# AFM_QFM_input.net
KiCad netlist of a schematic drawn in EAGLE
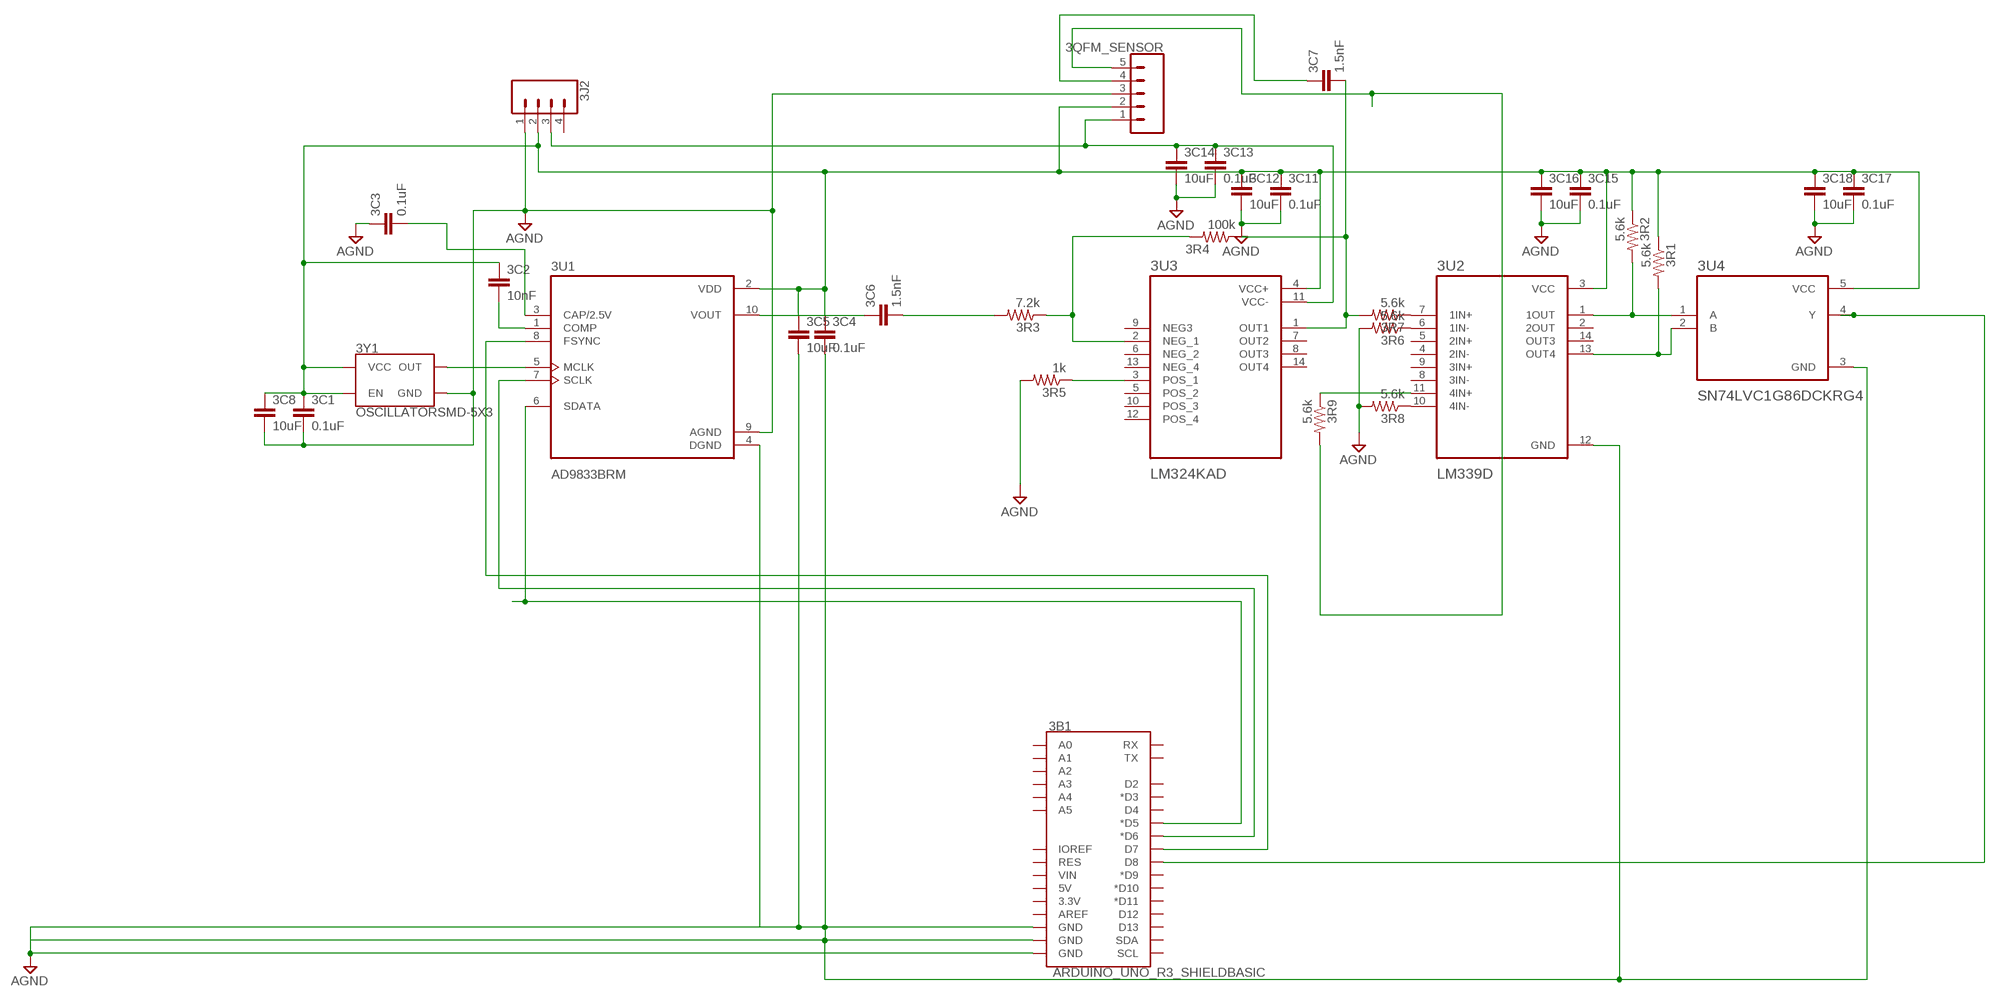
[diagram p0: schematic, sheet 1]

(export (version "E")
  (design (tool "Eeschema 10.0.6"))
  (components
    (comp (ref "3B1")
      (value "ARDUINO_UNO_R3_SHIELDBASIC")
      (footprint "eagle-import:UNO_R3_SHIELD")
      (libsource (lib "eagle-import") (part "ARDUINO_UNO_R3_SHIELDBASIC"))
    )
    (comp (ref "3C1")
      (value "0.1uF")
      (footprint "eagle-import:0603")
      (libsource (lib "eagle-import") (part "0.1UF-0603-100V-10%"))
    )
    (comp (ref "3C2")
      (value "10nF")
      (footprint "eagle-import:0603")
      (libsource (lib "eagle-import") (part "10NF-0603-50V-10%"))
    )
    (comp (ref "3C3")
      (value "0.1uF")
      (footprint "eagle-import:0603")
      (libsource (lib "eagle-import") (part "0.1UF-0603-100V-10%"))
    )
    (comp (ref "3C4")
      (value "0.1uF")
      (footprint "eagle-import:0603")
      (libsource (lib "eagle-import") (part "0.1UF-0603-100V-10%"))
    )
    (comp (ref "3C5")
      (value "10uF")
      (footprint "eagle-import:0805")
      (libsource (lib "eagle-import") (part "10UF-0805-10V-10%"))
    )
    (comp (ref "3C6")
      (value "1.5nF")
      (footprint "eagle-import:C0603")
      (libsource (lib "eagle-import") (part "C-EUC0603"))
    )
    (comp (ref "3C7")
      (value "1.5nF")
      (footprint "eagle-import:C0603")
      (libsource (lib "eagle-import") (part "C-EUC0603"))
    )
    (comp (ref "3C8")
      (value "10uF")
      (footprint "eagle-import:0805")
      (libsource (lib "eagle-import") (part "10UF-0805-10V-10%"))
    )
    (comp (ref "3C11")
      (value "0.1uF")
      (footprint "eagle-import:0603")
      (libsource (lib "eagle-import") (part "0.1UF-0603-100V-10%"))
    )
    (comp (ref "3C12")
      (value "10uF")
      (footprint "eagle-import:0805")
      (libsource (lib "eagle-import") (part "10UF-0805-10V-10%"))
    )
    (comp (ref "3C13")
      (value "0.1uF")
      (footprint "eagle-import:0603")
      (libsource (lib "eagle-import") (part "0.1UF-0603-100V-10%"))
    )
    (comp (ref "3C14")
      (value "10uF")
      (footprint "eagle-import:0805")
      (libsource (lib "eagle-import") (part "10UF-0805-10V-10%"))
    )
    (comp (ref "3C15")
      (value "0.1uF")
      (footprint "eagle-import:0603")
      (libsource (lib "eagle-import") (part "0.1UF-0603-100V-10%"))
    )
    (comp (ref "3C16")
      (value "10uF")
      (footprint "eagle-import:0805")
      (libsource (lib "eagle-import") (part "10UF-0805-10V-10%"))
    )
    (comp (ref "3C17")
      (value "0.1uF")
      (footprint "eagle-import:0603")
      (libsource (lib "eagle-import") (part "0.1UF-0603-100V-10%"))
    )
    (comp (ref "3C18")
      (value "10uF")
      (footprint "eagle-import:0805")
      (libsource (lib "eagle-import") (part "10UF-0805-10V-10%"))
    )
    (comp (ref "3J2")
      (value "CONN_04LONGPADS")
      (footprint "eagle-import:1X04_LONGPADS")
      (libsource (lib "eagle-import") (part "CONN_04LONGPADS"))
    )
    (comp (ref "3QFM_SENSOR")
      (value "CONN_05PTH_LONGPADS")
      (footprint "eagle-import:1X05_LONGPADS")
      (libsource (lib "eagle-import") (part "CONN_05PTH_LONGPADS"))
    )
    (comp (ref "3R1")
      (value "5.6k")
      (footprint "eagle-import:R0603")
      (libsource (lib "eagle-import") (part "R-US_R0603"))
    )
    (comp (ref "3R2")
      (value "5.6k")
      (footprint "eagle-import:R0603")
      (libsource (lib "eagle-import") (part "R-US_R0603"))
    )
    (comp (ref "3R3")
      (value "7.2k")
      (footprint "eagle-import:R0603")
      (libsource (lib "eagle-import") (part "R-US_R0603"))
    )
    (comp (ref "3R4")
      (value "100k")
      (footprint "eagle-import:R0603")
      (libsource (lib "eagle-import") (part "R-US_R0603"))
    )
    (comp (ref "3R5")
      (value "1k")
      (footprint "eagle-import:R0603")
      (libsource (lib "eagle-import") (part "R-US_R0603"))
    )
    (comp (ref "3R6")
      (value "5.6k")
      (footprint "eagle-import:R0603")
      (libsource (lib "eagle-import") (part "R-US_R0603"))
    )
    (comp (ref "3R7")
      (value "5.6k")
      (footprint "eagle-import:R0603")
      (libsource (lib "eagle-import") (part "R-US_R0603"))
    )
    (comp (ref "3R8")
      (value "5.6k")
      (footprint "eagle-import:R0603")
      (libsource (lib "eagle-import") (part "R-US_R0603"))
    )
    (comp (ref "3R9")
      (value "5.6k")
      (footprint "eagle-import:R0603")
      (libsource (lib "eagle-import") (part "R-US_R0603"))
    )
    (comp (ref "3U1")
      (value "AD9833BRM")
      (footprint "eagle-import:SOP50P490X110-10N")
      (fields (field (name "MF") "Analog Devices"))
      (libsource (lib "eagle-import") (part "AD9833BRM"))
    )
    (comp (ref "3U2")
      (value "LM339D")
      (footprint "eagle-import:SOIC127P600X175-14N")
      (fields (field (name "MF") "Texas Instruments"))
      (libsource (lib "eagle-import") (part "LM339D"))
    )
    (comp (ref "3U3")
      (value "LM324KAD")
      (footprint "eagle-import:SOIC127P600X175-14N")
      (fields (field (name "MF") "Texas Instruments"))
      (libsource (lib "eagle-import") (part "LM324KAD"))
    )
    (comp (ref "3U4")
      (value "SN74LVC1G86DCKRG4")
      (footprint "eagle-import:SOT65P210X110-5N")
      (fields (field (name "MF") "Texas Instruments"))
      (libsource (lib "eagle-import") (part "SN74LVC1G86DCKRG4"))
    )
    (comp (ref "3Y1")
      (value "OSCILLATORSMD-5X3")
      (footprint "eagle-import:OSCILLATOR-SMD-5X3.2")
      (libsource (lib "eagle-import") (part "OSCILLATORSMD-5X3"))
    )
  )
  (nets
    (net (code "1") (name "AGND") (class "Default")
      (node (ref "3B1") (pin "GND@0") (pinfunction "GND_GND@0") (pintype "bidirectional"))
      (node (ref "3B1") (pin "GND@1") (pinfunction "GND_GND@1") (pintype "bidirectional"))
      (node (ref "3B1") (pin "GND@2") (pinfunction "GND_GND@2") (pintype "bidirectional"))
      (node (ref "3C1") (pin "2") (pinfunction "2_2") (pintype "passive"))
      (node (ref "3C11") (pin "2") (pinfunction "2_2") (pintype "passive"))
      (node (ref "3C12") (pin "2") (pinfunction "2_2") (pintype "passive"))
      (node (ref "3C13") (pin "2") (pinfunction "2_2") (pintype "passive"))
      (node (ref "3C14") (pin "2") (pinfunction "2_2") (pintype "passive"))
      (node (ref "3C15") (pin "2") (pinfunction "2_2") (pintype "passive"))
      (node (ref "3C16") (pin "2") (pinfunction "2_2") (pintype "passive"))
      (node (ref "3C17") (pin "2") (pinfunction "2_2") (pintype "passive"))
      (node (ref "3C18") (pin "2") (pinfunction "2_2") (pintype "passive"))
      (node (ref "3C3") (pin "1") (pinfunction "1_1") (pintype "passive"))
      (node (ref "3C4") (pin "2") (pinfunction "2_2") (pintype "passive"))
      (node (ref "3C5") (pin "2") (pinfunction "2_2") (pintype "passive"))
      (node (ref "3C8") (pin "2") (pinfunction "2_2") (pintype "passive"))
      (node (ref "3J2") (pin "1") (pinfunction "1_1") (pintype "passive"))
      (node (ref "3QFM_SENSOR") (pin "3") (pinfunction "3_3") (pintype "passive"))
      (node (ref "3R5") (pin "2") (pinfunction "2_2") (pintype "passive"))
      (node (ref "3R6") (pin "2") (pinfunction "2_2") (pintype "passive"))
      (node (ref "3R8") (pin "2") (pinfunction "2_2") (pintype "passive"))
      (node (ref "3U1") (pin "4") (pinfunction "DGND_4") (pintype "power_in"))
      (node (ref "3U1") (pin "9") (pinfunction "AGND_9") (pintype "power_in"))
      (node (ref "3U2") (pin "12") (pinfunction "GND_12") (pintype "power_in"))
      (node (ref "3U4") (pin "3") (pinfunction "GND_3") (pintype "power_in"))
      (node (ref "3Y1") (pin "2") (pinfunction "GND_2") (pintype "bidirectional"))
    )
    (net (code "2") (name "Net-(3B1-*D5)") (class "Default")
      (node (ref "3B1") (pin "D5") (pinfunction "*D5_D5") (pintype "bidirectional"))
      (node (ref "3U1") (pin "6") (pinfunction "SDATA_6") (pintype "input"))
    )
    (net (code "3") (name "Net-(3B1-*D6)") (class "Default")
      (node (ref "3B1") (pin "D6") (pinfunction "*D6_D6") (pintype "bidirectional"))
      (node (ref "3U1") (pin "7") (pinfunction "SCLK_7") (pintype "input"))
    )
    (net (code "4") (name "Net-(3C6-Pad2)") (class "Default")
      (node (ref "3C6") (pin "2") (pinfunction "2_2") (pintype "passive"))
      (node (ref "3R3") (pin "2") (pinfunction "2_2") (pintype "passive"))
    )
    (net (code "5") (name "Net-(3C7-Pad1)") (class "Default")
      (node (ref "3C7") (pin "1") (pinfunction "1_1") (pintype "passive"))
      (node (ref "3QFM_SENSOR") (pin "4") (pinfunction "4_4") (pintype "passive"))
    )
    (net (code "6") (name "Net-(3QFM_SENSOR-Pad5)") (class "Default")
      (node (ref "3QFM_SENSOR") (pin "5") (pinfunction "5_5") (pintype "passive"))
      (node (ref "3R9") (pin "2") (pinfunction "2_2") (pintype "passive"))
    )
    (net (code "7") (name "Net-(3U1-CAP{slash}2.5V)") (class "Default")
      (node (ref "3C3") (pin "2") (pinfunction "2_2") (pintype "passive"))
      (node (ref "3U1") (pin "3") (pinfunction "CAP/2.5V_3") (pintype "input"))
    )
    (net (code "8") (name "Net-(3U1-COMP)") (class "Default")
      (node (ref "3C2") (pin "2") (pinfunction "2_2") (pintype "passive"))
      (node (ref "3U1") (pin "1") (pinfunction "COMP_1") (pintype "input"))
    )
    (net (code "9") (name "Net-(3U1-FSYNC)") (class "Default")
      (node (ref "3B1") (pin "D7") (pinfunction "D7_D7") (pintype "bidirectional"))
      (node (ref "3U1") (pin "8") (pinfunction "FSYNC_8") (pintype "input"))
    )
    (net (code "10") (name "Net-(3U1-MCLK)") (class "Default")
      (node (ref "3U1") (pin "5") (pinfunction "MCLK_5") (pintype "input"))
      (node (ref "3Y1") (pin "3") (pinfunction "OUT_3") (pintype "bidirectional"))
    )
    (net (code "11") (name "Net-(3U1-VDD)") (class "Default")
      (node (ref "3C1") (pin "1") (pinfunction "1_1") (pintype "passive"))
      (node (ref "3C11") (pin "1") (pinfunction "1_1") (pintype "passive"))
      (node (ref "3C12") (pin "1") (pinfunction "1_1") (pintype "passive"))
      (node (ref "3C15") (pin "1") (pinfunction "1_1") (pintype "passive"))
      (node (ref "3C16") (pin "1") (pinfunction "1_1") (pintype "passive"))
      (node (ref "3C17") (pin "1") (pinfunction "1_1") (pintype "passive"))
      (node (ref "3C18") (pin "1") (pinfunction "1_1") (pintype "passive"))
      (node (ref "3C2") (pin "1") (pinfunction "1_1") (pintype "passive"))
      (node (ref "3C4") (pin "1") (pinfunction "1_1") (pintype "passive"))
      (node (ref "3C5") (pin "1") (pinfunction "1_1") (pintype "passive"))
      (node (ref "3C8") (pin "1") (pinfunction "1_1") (pintype "passive"))
      (node (ref "3J2") (pin "2") (pinfunction "2_2") (pintype "passive"))
      (node (ref "3QFM_SENSOR") (pin "2") (pinfunction "2_2") (pintype "passive"))
      (node (ref "3R1") (pin "1") (pinfunction "1_1") (pintype "passive"))
      (node (ref "3R2") (pin "1") (pinfunction "1_1") (pintype "passive"))
      (node (ref "3U1") (pin "2") (pinfunction "VDD_2") (pintype "power_in"))
      (node (ref "3U2") (pin "3") (pinfunction "VCC_3") (pintype "power_in"))
      (node (ref "3U3") (pin "4") (pinfunction "VCC+_4") (pintype "power_in"))
      (node (ref "3U4") (pin "5") (pinfunction "VCC_5") (pintype "power_in"))
      (node (ref "3Y1") (pin "1") (pinfunction "EN_1") (pintype "bidirectional"))
      (node (ref "3Y1") (pin "4") (pinfunction "VCC_4") (pintype "bidirectional"))
    )
    (net (code "12") (name "Net-(3U1-VOUT)") (class "Default")
      (node (ref "3C6") (pin "1") (pinfunction "1_1") (pintype "passive"))
      (node (ref "3U1") (pin "10") (pinfunction "VOUT_10") (pintype "output"))
    )
    (net (code "13") (name "Net-(3U2-1IN+)") (class "Default")
      (node (ref "3R7") (pin "1") (pinfunction "1_1") (pintype "passive"))
      (node (ref "3U2") (pin "7") (pinfunction "1IN+_7") (pintype "input"))
    )
    (net (code "14") (name "Net-(3U2-1IN-)") (class "Default")
      (node (ref "3R6") (pin "1") (pinfunction "1_1") (pintype "passive"))
      (node (ref "3U2") (pin "6") (pinfunction "1IN-_6") (pintype "input"))
    )
    (net (code "15") (name "Net-(3U2-1OUT)") (class "Default")
      (node (ref "3R2") (pin "2") (pinfunction "2_2") (pintype "passive"))
      (node (ref "3U2") (pin "1") (pinfunction "1OUT_1") (pintype "output"))
      (node (ref "3U4") (pin "1") (pinfunction "A_1") (pintype "input"))
    )
    (net (code "16") (name "Net-(3U2-4IN+)") (class "Default")
      (node (ref "3R9") (pin "1") (pinfunction "1_1") (pintype "passive"))
      (node (ref "3U2") (pin "11") (pinfunction "4IN+_11") (pintype "input"))
    )
    (net (code "17") (name "Net-(3U2-4IN-)") (class "Default")
      (node (ref "3R8") (pin "1") (pinfunction "1_1") (pintype "passive"))
      (node (ref "3U2") (pin "10") (pinfunction "4IN-_10") (pintype "input"))
    )
    (net (code "18") (name "Net-(3U2-OUT4)") (class "Default")
      (node (ref "3R1") (pin "2") (pinfunction "2_2") (pintype "passive"))
      (node (ref "3U2") (pin "13") (pinfunction "OUT4_13") (pintype "output"))
      (node (ref "3U4") (pin "2") (pinfunction "B_2") (pintype "input"))
    )
    (net (code "19") (name "Net-(3U3-NEG_1)") (class "Default")
      (node (ref "3R3") (pin "1") (pinfunction "1_1") (pintype "passive"))
      (node (ref "3R4") (pin "2") (pinfunction "2_2") (pintype "passive"))
      (node (ref "3U3") (pin "2") (pinfunction "NEG_1_2") (pintype "input"))
    )
    (net (code "20") (name "Net-(3U3-OUT1)") (class "Default")
      (node (ref "3C7") (pin "2") (pinfunction "2_2") (pintype "passive"))
      (node (ref "3R4") (pin "1") (pinfunction "1_1") (pintype "passive"))
      (node (ref "3R7") (pin "2") (pinfunction "2_2") (pintype "passive"))
      (node (ref "3U3") (pin "1") (pinfunction "OUT1_1") (pintype "output"))
    )
    (net (code "21") (name "Net-(3U3-POS_1)") (class "Default")
      (node (ref "3R5") (pin "1") (pinfunction "1_1") (pintype "passive"))
      (node (ref "3U3") (pin "3") (pinfunction "POS_1_3") (pintype "input"))
    )
    (net (code "22") (name "Net-(3U3-VCC-)") (class "Default")
      (node (ref "3C13") (pin "1") (pinfunction "1_1") (pintype "passive"))
      (node (ref "3C14") (pin "1") (pinfunction "1_1") (pintype "passive"))
      (node (ref "3J2") (pin "3") (pinfunction "3_3") (pintype "passive"))
      (node (ref "3QFM_SENSOR") (pin "1") (pinfunction "1_1") (pintype "passive"))
      (node (ref "3U3") (pin "11") (pinfunction "VCC-_11") (pintype "power_in"))
    )
    (net (code "23") (name "Net-(3U4-Y)") (class "Default")
      (node (ref "3B1") (pin "D8") (pinfunction "D8_D8") (pintype "bidirectional"))
      (node (ref "3U4") (pin "4") (pinfunction "Y_4") (pintype "output"))
    )
    (net (code "24") (name "unconnected-(3B1-*D3-PadD3)") (class "Default")
      (node (ref "3B1") (pin "D3") (pinfunction "*D3_D3") (pintype "bidirectional"))
    )
    (net (code "25") (name "unconnected-(3B1-*D9-PadD9)") (class "Default")
      (node (ref "3B1") (pin "D9") (pinfunction "*D9_D9") (pintype "bidirectional"))
    )
    (net (code "26") (name "unconnected-(3B1-*D10-PadD10)") (class "Default")
      (node (ref "3B1") (pin "D10") (pinfunction "*D10_D10") (pintype "bidirectional"))
    )
    (net (code "27") (name "unconnected-(3B1-*D11-PadD11)") (class "Default")
      (node (ref "3B1") (pin "D11") (pinfunction "*D11_D11") (pintype "bidirectional"))
    )
    (net (code "28") (name "unconnected-(3B1-Pad3.3V)") (class "Default")
      (node (ref "3B1") (pin "3.3V") (pinfunction "3.3V_3.3V") (pintype "bidirectional"))
    )
    (net (code "29") (name "unconnected-(3B1-Pad5V)") (class "Default")
      (node (ref "3B1") (pin "5V") (pinfunction "5V_5V") (pintype "bidirectional"))
    )
    (net (code "30") (name "unconnected-(3B1-PadA0)") (class "Default")
      (node (ref "3B1") (pin "A0") (pinfunction "A0_A0") (pintype "bidirectional"))
    )
    (net (code "31") (name "unconnected-(3B1-PadA1)") (class "Default")
      (node (ref "3B1") (pin "A1") (pinfunction "A1_A1") (pintype "bidirectional"))
    )
    (net (code "32") (name "unconnected-(3B1-PadA2)") (class "Default")
      (node (ref "3B1") (pin "A2") (pinfunction "A2_A2") (pintype "bidirectional"))
    )
    (net (code "33") (name "unconnected-(3B1-PadA3)") (class "Default")
      (node (ref "3B1") (pin "A3") (pinfunction "A3_A3") (pintype "bidirectional"))
    )
    (net (code "34") (name "unconnected-(3B1-PadA4)") (class "Default")
      (node (ref "3B1") (pin "A4") (pinfunction "A4_A4") (pintype "bidirectional"))
    )
    (net (code "35") (name "unconnected-(3B1-PadA5)") (class "Default")
      (node (ref "3B1") (pin "A5") (pinfunction "A5_A5") (pintype "bidirectional"))
    )
    (net (code "36") (name "unconnected-(3B1-PadAREF)") (class "Default")
      (node (ref "3B1") (pin "AREF") (pinfunction "AREF_AREF") (pintype "bidirectional"))
    )
    (net (code "37") (name "unconnected-(3B1-PadD2)") (class "Default")
      (node (ref "3B1") (pin "D2") (pinfunction "D2_D2") (pintype "bidirectional"))
    )
    (net (code "38") (name "unconnected-(3B1-PadD4)") (class "Default")
      (node (ref "3B1") (pin "D4") (pinfunction "D4_D4") (pintype "bidirectional"))
    )
    (net (code "39") (name "unconnected-(3B1-PadD12)") (class "Default")
      (node (ref "3B1") (pin "D12") (pinfunction "D12_D12") (pintype "bidirectional"))
    )
    (net (code "40") (name "unconnected-(3B1-PadD13)") (class "Default")
      (node (ref "3B1") (pin "D13") (pinfunction "D13_D13") (pintype "bidirectional"))
    )
    (net (code "41") (name "unconnected-(3B1-PadIOREF)") (class "Default")
      (node (ref "3B1") (pin "IOREF") (pinfunction "IOREF_IOREF") (pintype "bidirectional"))
    )
    (net (code "42") (name "unconnected-(3B1-PadRES)") (class "Default")
      (node (ref "3B1") (pin "RES") (pinfunction "RES_RES") (pintype "bidirectional"))
    )
    (net (code "43") (name "unconnected-(3B1-PadRX)") (class "Default")
      (node (ref "3B1") (pin "RX") (pinfunction "RX_RX") (pintype "bidirectional"))
    )
    (net (code "44") (name "unconnected-(3B1-PadSCL)") (class "Default")
      (node (ref "3B1") (pin "SCL") (pinfunction "SCL_SCL") (pintype "bidirectional"))
    )
    (net (code "45") (name "unconnected-(3B1-PadSDA)") (class "Default")
      (node (ref "3B1") (pin "SDA") (pinfunction "SDA_SDA") (pintype "bidirectional"))
    )
    (net (code "46") (name "unconnected-(3B1-PadTX)") (class "Default")
      (node (ref "3B1") (pin "TX") (pinfunction "TX_TX") (pintype "bidirectional"))
    )
    (net (code "47") (name "unconnected-(3B1-PadVIN)") (class "Default")
      (node (ref "3B1") (pin "VIN") (pinfunction "VIN_VIN") (pintype "bidirectional"))
    )
    (net (code "48") (name "unconnected-(3J2-Pad4)") (class "Default")
      (node (ref "3J2") (pin "4") (pinfunction "4_4") (pintype "passive"))
    )
    (net (code "49") (name "unconnected-(3U2-2IN+-Pad5)") (class "Default")
      (node (ref "3U2") (pin "5") (pinfunction "2IN+_5") (pintype "input"))
    )
    (net (code "50") (name "unconnected-(3U2-2IN--Pad4)") (class "Default")
      (node (ref "3U2") (pin "4") (pinfunction "2IN-_4") (pintype "input"))
    )
    (net (code "51") (name "unconnected-(3U2-2OUT-Pad2)") (class "Default")
      (node (ref "3U2") (pin "2") (pinfunction "2OUT_2") (pintype "output"))
    )
    (net (code "52") (name "unconnected-(3U2-3IN+-Pad9)") (class "Default")
      (node (ref "3U2") (pin "9") (pinfunction "3IN+_9") (pintype "input"))
    )
    (net (code "53") (name "unconnected-(3U2-3IN--Pad8)") (class "Default")
      (node (ref "3U2") (pin "8") (pinfunction "3IN-_8") (pintype "input"))
    )
    (net (code "54") (name "unconnected-(3U2-OUT3-Pad14)") (class "Default")
      (node (ref "3U2") (pin "14") (pinfunction "OUT3_14") (pintype "output"))
    )
    (net (code "55") (name "unconnected-(3U3-NEG3-Pad9)") (class "Default")
      (node (ref "3U3") (pin "9") (pinfunction "NEG3_9") (pintype "input"))
    )
    (net (code "56") (name "unconnected-(3U3-NEG_2-Pad6)") (class "Default")
      (node (ref "3U3") (pin "6") (pinfunction "NEG_2_6") (pintype "input"))
    )
    (net (code "57") (name "unconnected-(3U3-NEG_4-Pad13)") (class "Default")
      (node (ref "3U3") (pin "13") (pinfunction "NEG_4_13") (pintype "input"))
    )
    (net (code "58") (name "unconnected-(3U3-OUT2-Pad7)") (class "Default")
      (node (ref "3U3") (pin "7") (pinfunction "OUT2_7") (pintype "output"))
    )
    (net (code "59") (name "unconnected-(3U3-OUT3-Pad8)") (class "Default")
      (node (ref "3U3") (pin "8") (pinfunction "OUT3_8") (pintype "output"))
    )
    (net (code "60") (name "unconnected-(3U3-OUT4-Pad14)") (class "Default")
      (node (ref "3U3") (pin "14") (pinfunction "OUT4_14") (pintype "output"))
    )
    (net (code "61") (name "unconnected-(3U3-POS_2-Pad5)") (class "Default")
      (node (ref "3U3") (pin "5") (pinfunction "POS_2_5") (pintype "input"))
    )
    (net (code "62") (name "unconnected-(3U3-POS_3-Pad10)") (class "Default")
      (node (ref "3U3") (pin "10") (pinfunction "POS_3_10") (pintype "input"))
    )
    (net (code "63") (name "unconnected-(3U3-POS_4-Pad12)") (class "Default")
      (node (ref "3U3") (pin "12") (pinfunction "POS_4_12") (pintype "input"))
    )
  )
)
